# HIH6130_Breakout.net
KiCad netlist of a schematic drawn in EAGLE
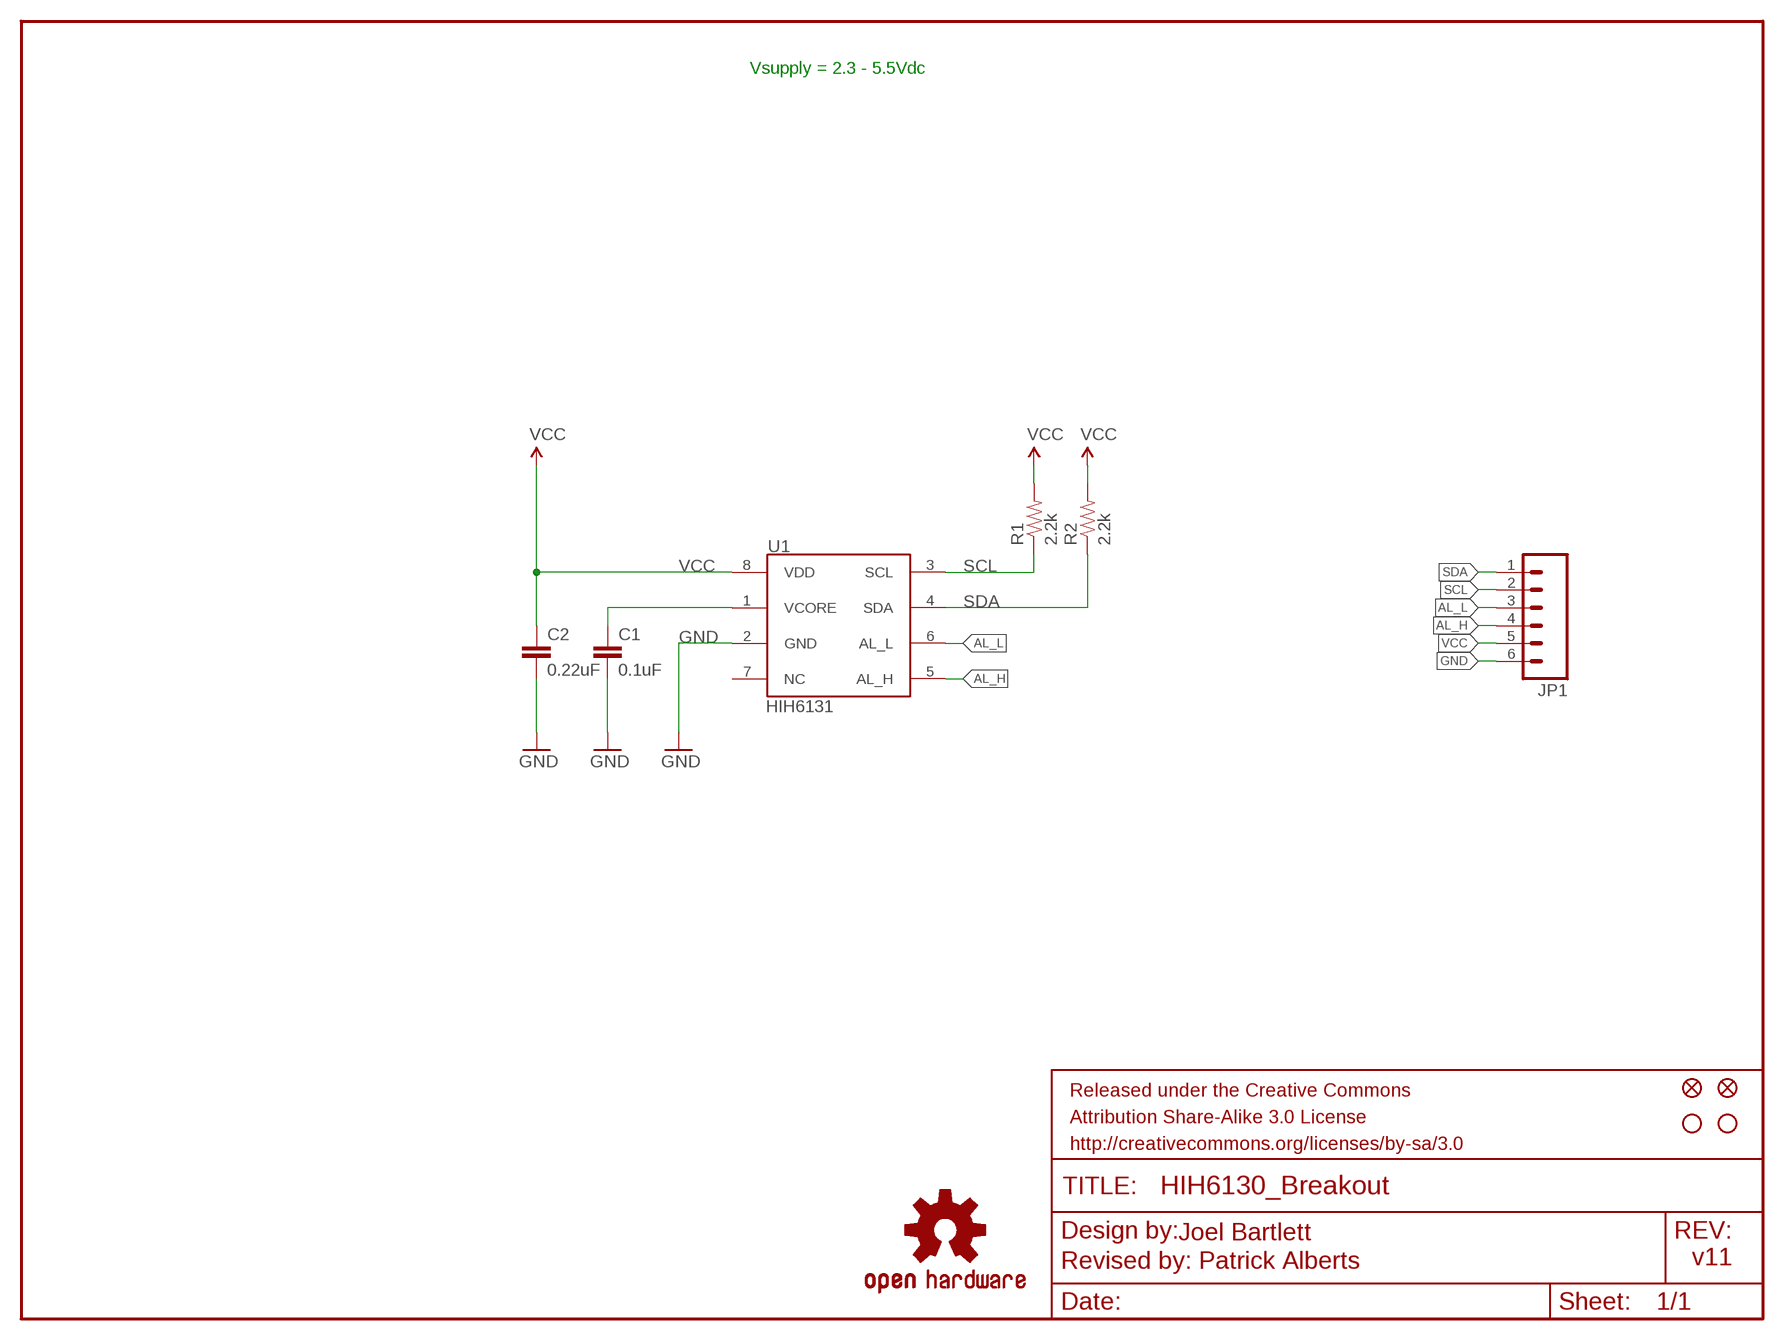
[diagram p0: schematic, sheet 1]

(export (version "E")
  (design (tool "Eeschema 10.0.6"))
  (components
    (comp (ref "C1")
      (value "0.1uF")
      (footprint "eagle-import:0603-CAP")
      (libsource (lib "eagle-import") (part "0.1UF-25V(+80/-20%)(0603)"))
    )
    (comp (ref "C2")
      (value "0.22uF")
      (footprint "eagle-import:0603-CAP")
      (libsource (lib "eagle-import") (part "0.22UF-25V-10%(0603)"))
    )
    (comp (ref "FRAME1")
      (value "FRAME-LETTER")
      (footprint "eagle-import:CREATIVE_COMMONS")
      (libsource (lib "eagle-import") (part "FRAME-LETTER"))
    )
    (comp (ref "JP1")
      (value "M06SIP")
      (footprint "eagle-import:1X06")
      (libsource (lib "eagle-import") (part "M06SIP"))
    )
    (comp (ref "JP2")
      (value "FIDUCIALUFIDUCIAL")
      (footprint "eagle-import:MICRO-FIDUCIAL")
      (libsource (lib "eagle-import") (part "FIDUCIALUFIDUCIAL"))
    )
    (comp (ref "JP3")
      (value "STAND-OFFTIGHT")
      (footprint "eagle-import:STAND-OFF-TIGHT")
      (libsource (lib "eagle-import") (part "STAND-OFFTIGHT"))
    )
    (comp (ref "JP4")
      (value "STAND-OFFTIGHT")
      (footprint "eagle-import:STAND-OFF-TIGHT")
      (libsource (lib "eagle-import") (part "STAND-OFFTIGHT"))
    )
    (comp (ref "JP5")
      (value "FIDUCIALUFIDUCIAL")
      (footprint "eagle-import:MICRO-FIDUCIAL")
      (libsource (lib "eagle-import") (part "FIDUCIALUFIDUCIAL"))
    )
    (comp (ref "R1")
      (value "2.2k")
      (footprint "eagle-import:0603-RES")
      (libsource (lib "eagle-import") (part "2.2KOHM1/10W1%(0603)"))
    )
    (comp (ref "R2")
      (value "2.2k")
      (footprint "eagle-import:0603-RES")
      (libsource (lib "eagle-import") (part "2.2KOHM1/10W1%(0603)"))
    )
    (comp (ref "U$2")
      (value "OSHW-LOGOS")
      (footprint "eagle-import:OSHW-LOGO-S")
      (libsource (lib "eagle-import") (part "OSHW-LOGOS"))
    )
    (comp (ref "U1")
      (value "HIH6131")
      (footprint "eagle-import:SOIC8")
      (libsource (lib "eagle-import") (part "HIH6131"))
    )
  )
  (nets
    (net (code "1") (name "AL_H") (class "Default")
      (node (ref "JP1") (pin "4") (pinfunction "4_4") (pintype "passive"))
      (node (ref "U1") (pin "5") (pinfunction "AL_H_5") (pintype "bidirectional"))
    )
    (net (code "2") (name "AL_L") (class "Default")
      (node (ref "JP1") (pin "3") (pinfunction "3_3") (pintype "passive"))
      (node (ref "U1") (pin "6") (pinfunction "AL_L_6") (pintype "bidirectional"))
    )
    (net (code "3") (name "GND") (class "Default")
      (node (ref "C1") (pin "2") (pinfunction "2_2") (pintype "passive"))
      (node (ref "C2") (pin "2") (pinfunction "2_2") (pintype "passive"))
      (node (ref "JP1") (pin "6") (pinfunction "6_6") (pintype "passive"))
      (node (ref "U1") (pin "2") (pinfunction "GND_2") (pintype "bidirectional"))
    )
    (net (code "4") (name "Net-(U1-VCORE)") (class "Default")
      (node (ref "C1") (pin "1") (pinfunction "1_1") (pintype "passive"))
      (node (ref "U1") (pin "1") (pinfunction "VCORE_1") (pintype "bidirectional"))
    )
    (net (code "5") (name "SCL") (class "Default")
      (node (ref "JP1") (pin "2") (pinfunction "2_2") (pintype "passive"))
      (node (ref "R1") (pin "1") (pinfunction "1_1") (pintype "passive"))
      (node (ref "U1") (pin "3") (pinfunction "SCL_3") (pintype "bidirectional"))
    )
    (net (code "6") (name "SDA") (class "Default")
      (node (ref "JP1") (pin "1") (pinfunction "1_1") (pintype "passive"))
      (node (ref "R2") (pin "1") (pinfunction "1_1") (pintype "passive"))
      (node (ref "U1") (pin "4") (pinfunction "SDA_4") (pintype "bidirectional"))
    )
    (net (code "7") (name "VCC") (class "Default")
      (node (ref "C2") (pin "1") (pinfunction "1_1") (pintype "passive"))
      (node (ref "JP1") (pin "5") (pinfunction "5_5") (pintype "passive"))
      (node (ref "R1") (pin "2") (pinfunction "2_2") (pintype "passive"))
      (node (ref "R2") (pin "2") (pinfunction "2_2") (pintype "passive"))
      (node (ref "U1") (pin "8") (pinfunction "VDD_8") (pintype "bidirectional"))
    )
    (net (code "8") (name "unconnected-(U1-NC-Pad7)") (class "Default")
      (node (ref "U1") (pin "7") (pinfunction "NC_7") (pintype "bidirectional"))
    )
  )
)
